# headers.net
KiCad netlist of a schematic drawn in Altium Designer
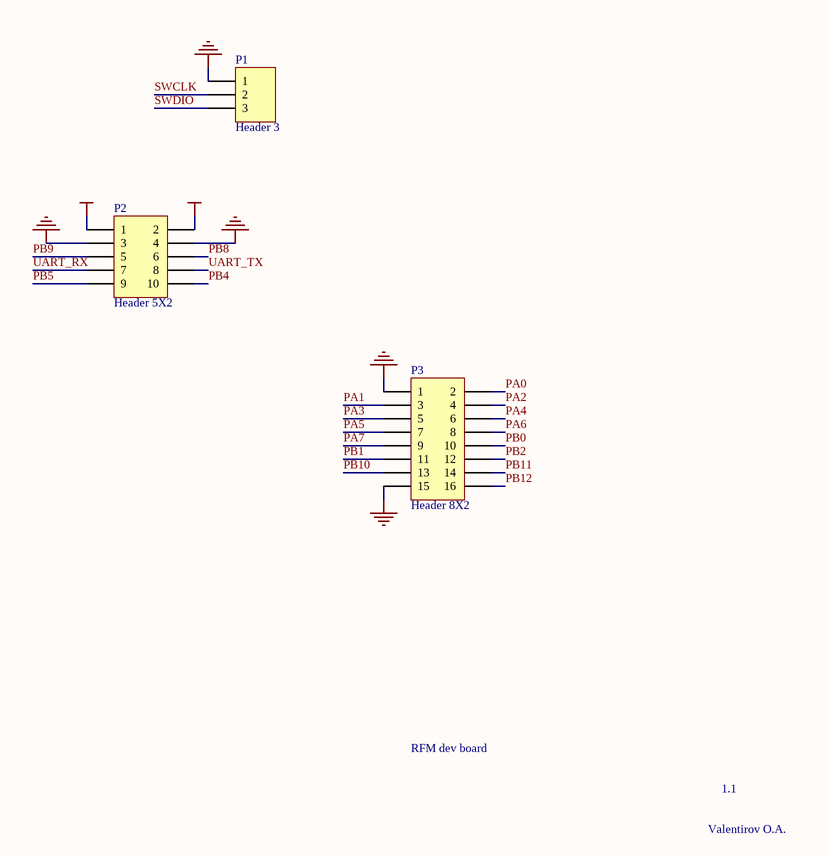
[diagram p0: headers.SchDoc]

(export (version "E")
  (design (tool "Eeschema 10.0.6"))
  (components
    (comp (ref "P1")
      (value "Header 3")
      (footprint "HDR1X3")
      (description "Header, 3-Pin")
      (fields (field (name "PUBLISHER") "Altium Limited"))
      (libsource (lib "Miscellaneous Connectors") (part "Header 3"))
    )
    (comp (ref "P2")
      (value "Header 5X2")
      (footprint "HDR2X5")
      (description "Header, 5-Pin, Dual row")
      (fields (field (name "PUBLISHER") "Altium Limited"))
      (libsource (lib "Miscellaneous Connectors") (part "Header 5X2"))
    )
    (comp (ref "P3")
      (value "Header 8X2")
      (footprint "HDR2X8")
      (description "Header, 8-Pin, Dual row")
      (fields (field (name "PUBLISHER") "Altium Limited"))
      (libsource (lib "Miscellaneous Connectors") (part "Header 8X2"))
    )
  )
  (nets
    (net (code "1") (name "/PA0") (class "Default")
      (node (ref "P3") (pin "2") (pinfunction "2_2") (pintype "passive"))
    )
    (net (code "2") (name "/PA1") (class "Default")
      (node (ref "P3") (pin "3") (pinfunction "3_3") (pintype "passive"))
    )
    (net (code "3") (name "/PA2") (class "Default")
      (node (ref "P3") (pin "4") (pinfunction "4_4") (pintype "passive"))
    )
    (net (code "4") (name "/PA3") (class "Default")
      (node (ref "P3") (pin "5") (pinfunction "5_5") (pintype "passive"))
    )
    (net (code "5") (name "/PA4") (class "Default")
      (node (ref "P3") (pin "6") (pinfunction "6_6") (pintype "passive"))
    )
    (net (code "6") (name "/PA5") (class "Default")
      (node (ref "P3") (pin "7") (pinfunction "7_7") (pintype "passive"))
    )
    (net (code "7") (name "/PA6") (class "Default")
      (node (ref "P3") (pin "8") (pinfunction "8_8") (pintype "passive"))
    )
    (net (code "8") (name "/PA7") (class "Default")
      (node (ref "P3") (pin "9") (pinfunction "9_9") (pintype "passive"))
    )
    (net (code "9") (name "/PB0") (class "Default")
      (node (ref "P3") (pin "10") (pinfunction "10_10") (pintype "passive"))
    )
    (net (code "10") (name "/PB1") (class "Default")
      (node (ref "P3") (pin "11") (pinfunction "11_11") (pintype "passive"))
    )
    (net (code "11") (name "/PB2") (class "Default")
      (node (ref "P3") (pin "12") (pinfunction "12_12") (pintype "passive"))
    )
    (net (code "12") (name "/PB4") (class "Default")
      (node (ref "P2") (pin "10") (pinfunction "10_10") (pintype "passive"))
    )
    (net (code "13") (name "/PB5") (class "Default")
      (node (ref "P2") (pin "9") (pinfunction "9_9") (pintype "passive"))
    )
    (net (code "14") (name "/PB8") (class "Default")
      (node (ref "P2") (pin "6") (pinfunction "6_6") (pintype "passive"))
    )
    (net (code "15") (name "/PB9") (class "Default")
      (node (ref "P2") (pin "5") (pinfunction "5_5") (pintype "passive"))
    )
    (net (code "16") (name "/PB10") (class "Default")
      (node (ref "P3") (pin "13") (pinfunction "13_13") (pintype "passive"))
    )
    (net (code "17") (name "/PB11") (class "Default")
      (node (ref "P3") (pin "14") (pinfunction "14_14") (pintype "passive"))
    )
    (net (code "18") (name "/PB12") (class "Default")
      (node (ref "P3") (pin "16") (pinfunction "16_16") (pintype "passive"))
    )
    (net (code "19") (name "/SWCLK") (class "Default")
      (node (ref "P1") (pin "2") (pinfunction "2_2") (pintype "passive"))
    )
    (net (code "20") (name "/SWDIO") (class "Default")
      (node (ref "P1") (pin "3") (pinfunction "3_3") (pintype "passive"))
    )
    (net (code "21") (name "/UART_RX") (class "Default")
      (node (ref "P2") (pin "7") (pinfunction "7_7") (pintype "passive"))
    )
    (net (code "22") (name "/UART_TX") (class "Default")
      (node (ref "P2") (pin "8") (pinfunction "8_8") (pintype "passive"))
    )
    (net (code "23") (name "GND") (class "Default")
      (node (ref "P1") (pin "1") (pinfunction "1_1") (pintype "passive"))
      (node (ref "P2") (pin "3") (pinfunction "3_3") (pintype "passive"))
      (node (ref "P2") (pin "4") (pinfunction "4_4") (pintype "passive"))
      (node (ref "P3") (pin "1") (pinfunction "1_1") (pintype "passive"))
      (node (ref "P3") (pin "15") (pinfunction "15_15") (pintype "passive"))
    )
    (net (code "24") (name "VCC") (class "Default")
      (node (ref "P2") (pin "1") (pinfunction "1_1") (pintype "passive"))
      (node (ref "P2") (pin "2") (pinfunction "2_2") (pintype "passive"))
    )
  )
)
